# ConectoresEntrada.net
KiCad netlist of a schematic drawn in Altium Designer
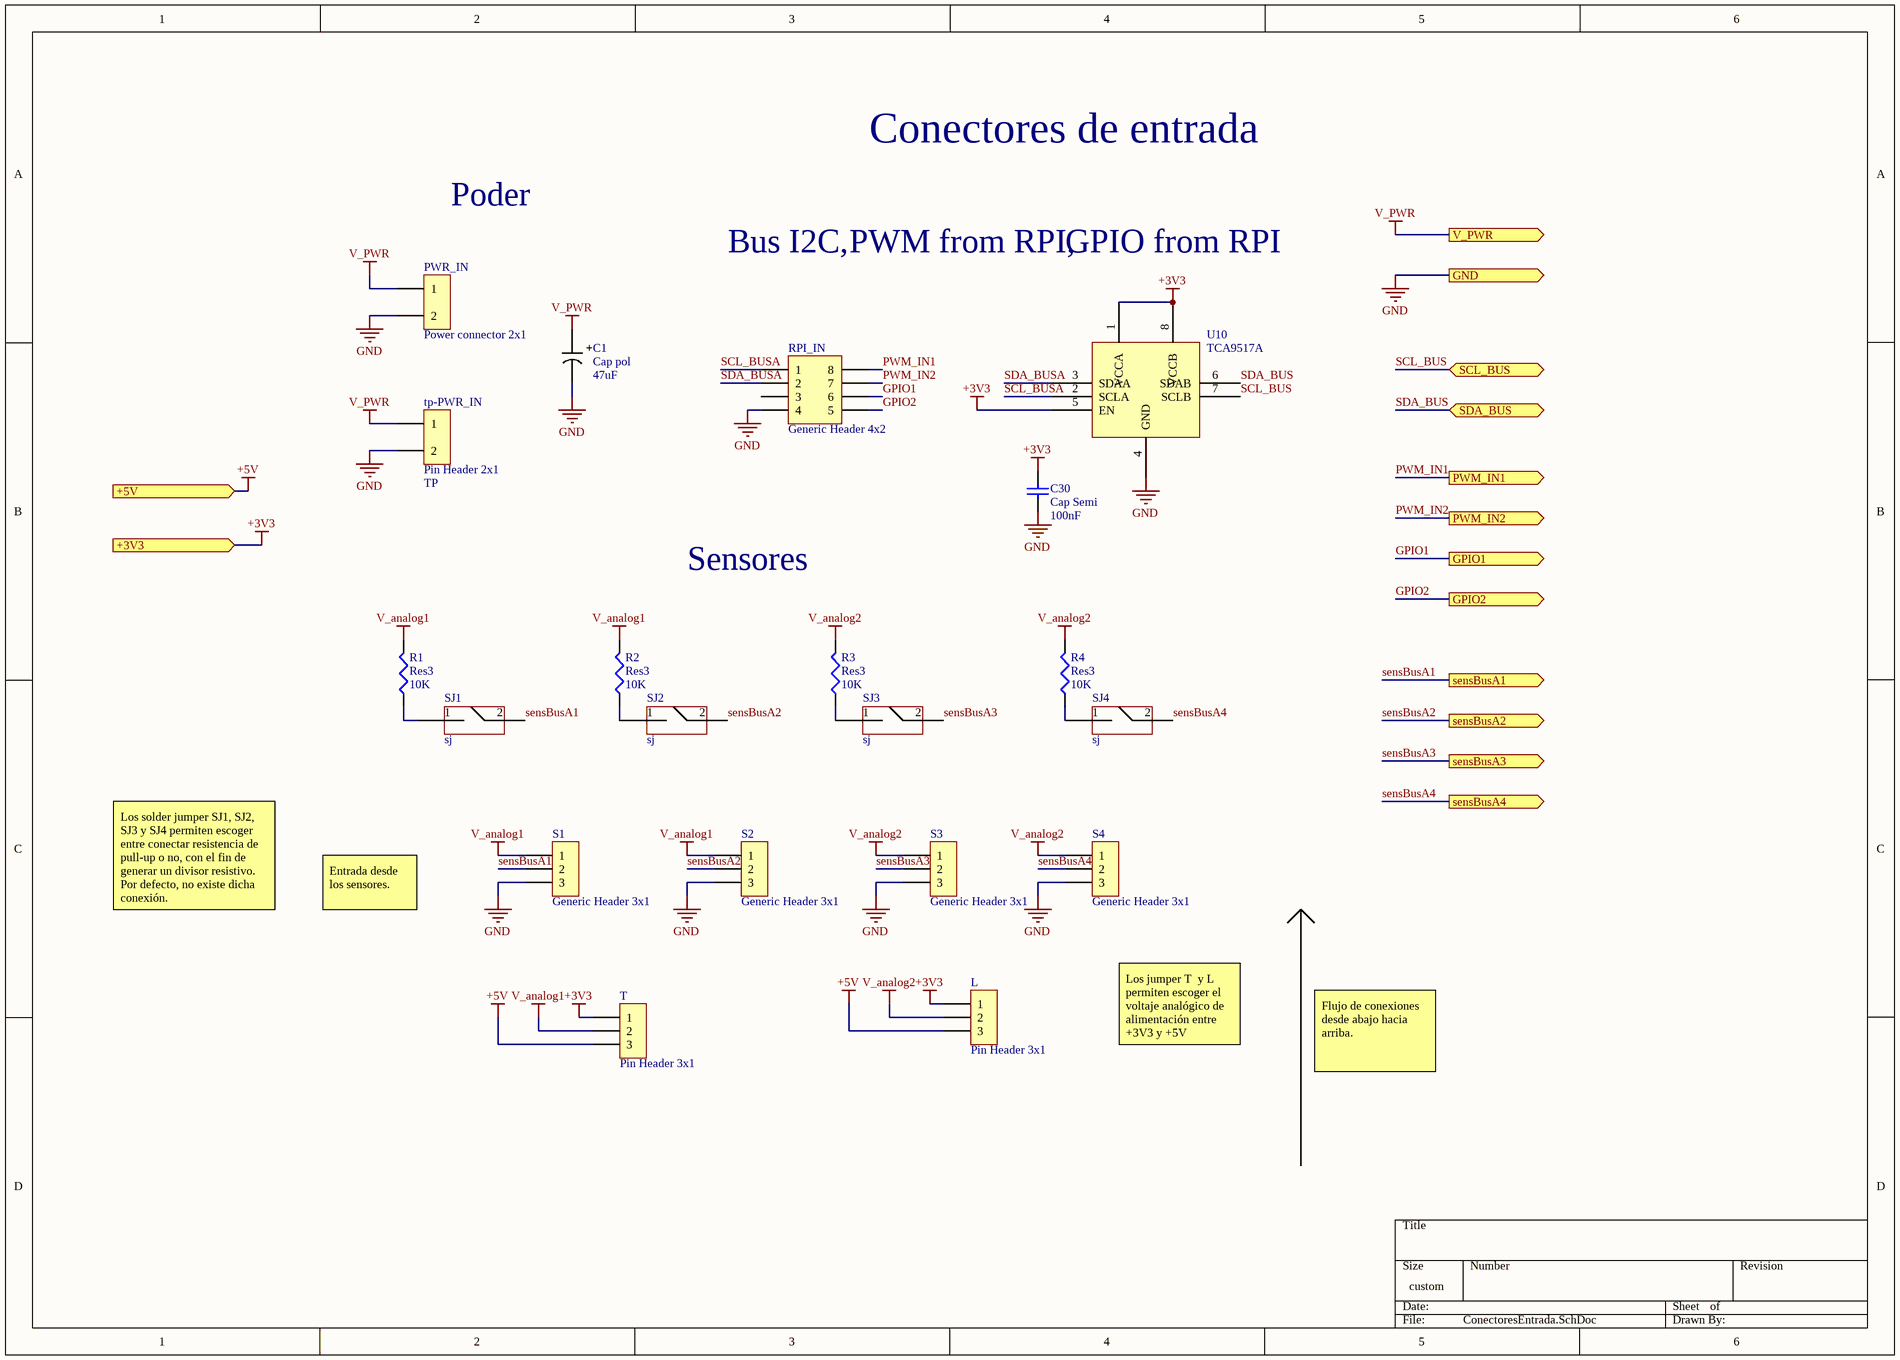
[diagram p0: ConectoresEntrada.SchDoc]

(export (version "E")
  (design (tool "Eeschema 10.0.6"))
  (components
    (comp (ref "C1")
      (value "Cap pol")
      (footprint "CAP_SMD_Electrolytic_10x10")
      (description "Electrolytic Aluminium Capacitor")
      (fields
        (field (name "MANUFACTURER") "Lelon")
        (field (name "MANUFACTURER PART NUMBER") "VEJ470M1HTR-1010")
        (field (name "ALTIUM_VALUE") "47uF")
      )
      (libsource (lib "IoWLabs") (part "Cap pol"))
    )
    (comp (ref "C30")
      (value "Cap Semi")
      (footprint "1608[0603]")
      (description "Capacitor (Semiconductor SIM Model)")
      (fields
        (field (name "ALTIUM_VALUE") "100nF")
        (field (name "MANUFACTURER") "Taiyo Yuden")
        (field (name "MANUFACTURER PART NUMBER") "UMK107B104KAHT")
        (field (name "PUBLISHER") "Altium Limited")
      )
      (libsource (lib "Miscellaneous Devices") (part "Cap Semi"))
    )
    (comp (ref "L")
      (value "Pin Header 3x1")
      (footprint "HDR-TH_3P-P2.54-V")
      (description "Pin Header 3pos, 1 row, 2.54 pitch")
      (fields
        (field (name "MANUFACTURER") "CJT(Changjiang Connectors)")
        (field (name "MANUFACTURER PART NUMBER") "A2541WV-3P")
      )
      (libsource (lib "IoWLabsConnectors") (part "Header - 3x1c"))
    )
    (comp (ref "PWR_IN")
      (value "Power connector 2x1")
      (footprint "CONN-TH_430450212")
      (description "Generic Header Power 2pos")
      (fields (field (name "MANUFACTURER") "MOLEX") (field (name "MANUFACTURER PART NUMBER") "430450212"))
      (libsource (lib "IoWLabsConnectors") (part "PC - 2X1"))
    )
    (comp (ref "R1")
      (value "Res3")
      (footprint "J1-0603")
      (description "Resistor")
      (fields
        (field (name "ALTIUM_VALUE") "10K")
        (field (name "MANUFACTURER") "PANASONIC")
        (field (name "MANUFACTURER PART NUMBER") "ERJPB3B1002V")
        (field (name "PUBLISHER") "Altium Limited")
      )
      (libsource (lib "Miscellaneous Devices") (part "Res3"))
    )
    (comp (ref "R2")
      (value "Res3")
      (footprint "J1-0603")
      (description "Resistor")
      (fields
        (field (name "ALTIUM_VALUE") "10K")
        (field (name "MANUFACTURER") "PANASONIC")
        (field (name "MANUFACTURER PART NUMBER") "ERJPB3B1002V")
        (field (name "PUBLISHER") "Altium Limited")
      )
      (libsource (lib "Miscellaneous Devices") (part "Res3"))
    )
    (comp (ref "R3")
      (value "Res3")
      (footprint "J1-0603")
      (description "Resistor")
      (fields
        (field (name "ALTIUM_VALUE") "10K")
        (field (name "MANUFACTURER") "PANASONIC")
        (field (name "MANUFACTURER PART NUMBER") "ERJPB3B1002V")
        (field (name "PUBLISHER") "Altium Limited")
      )
      (libsource (lib "Miscellaneous Devices") (part "Res3"))
    )
    (comp (ref "R4")
      (value "Res3")
      (footprint "J1-0603")
      (description "Resistor")
      (fields
        (field (name "ALTIUM_VALUE") "10K")
        (field (name "MANUFACTURER PART NUMBER") "ERJPB3B1002V")
        (field (name "MANUFACTURER") "PANASONIC")
        (field (name "PUBLISHER") "Altium Limited")
      )
      (libsource (lib "Miscellaneous Devices") (part "Res3"))
    )
    (comp (ref "RPI_IN")
      (value "Generic Header 4x2")
      (footprint "CONN-TH_8P-P2.54-V-M_15477608")
      (description "Generic Header 8 pos, 2 row, 2.54 pitch")
      (fields (field (name "MANUFACTURER") "MOLEX") (field (name "MANUFACTURER PART NUMBER") "15477608"))
      (libsource (lib "IoWLabsConnectors") (part "Header - 4x2"))
    )
    (comp (ref "S1")
      (value "Generic Header 3x1")
      (footprint "CONN-TH_A2547WV-3P")
      (description "Generic Header 3pos, 1 row, 2.54 pitch")
      (fields
        (field (name "MANUFACTURER") "CJT(Changjiang Connectors)")
        (field (name "MANUFACTURER PART NUMBER") "A2547WV-3P")
      )
      (libsource (lib "IoWLabsConnectors") (part "Header - 3x1"))
    )
    (comp (ref "S2")
      (value "Generic Header 3x1")
      (footprint "CONN-TH_A2547WV-3P")
      (description "Generic Header 3pos, 1 row, 2.54 pitch")
      (fields
        (field (name "MANUFACTURER") "CJT(Changjiang Connectors)")
        (field (name "MANUFACTURER PART NUMBER") "A2547WV-3P")
      )
      (libsource (lib "IoWLabsConnectors") (part "Header - 3x1"))
    )
    (comp (ref "S3")
      (value "Generic Header 3x1")
      (footprint "CONN-TH_A2547WV-3P")
      (description "Generic Header 3pos, 1 row, 2.54 pitch")
      (fields
        (field (name "MANUFACTURER") "CJT(Changjiang Connectors)")
        (field (name "MANUFACTURER PART NUMBER") "A2547WV-3P")
      )
      (libsource (lib "IoWLabsConnectors") (part "Header - 3x1"))
    )
    (comp (ref "S4")
      (value "Generic Header 3x1")
      (footprint "CONN-TH_A2547WV-3P")
      (description "Generic Header 3pos, 1 row, 2.54 pitch")
      (fields
        (field (name "MANUFACTURER") "CJT(Changjiang Connectors)")
        (field (name "MANUFACTURER PART NUMBER") "A2547WV-3P")
      )
      (libsource (lib "IoWLabsConnectors") (part "Header - 3x1"))
    )
    (comp (ref "SJ1")
      (value "sj")
      (footprint "SJ2")
      (description "solder jumper generic")
      (libsource (lib "IoWLabs") (part "Jumper"))
    )
    (comp (ref "SJ2")
      (value "sj")
      (footprint "SJ2")
      (description "solder jumper generic")
      (libsource (lib "IoWLabs") (part "Jumper"))
    )
    (comp (ref "SJ3")
      (value "sj")
      (footprint "SJ2")
      (description "solder jumper generic")
      (libsource (lib "IoWLabs") (part "Jumper"))
    )
    (comp (ref "SJ4")
      (value "sj")
      (footprint "SJ2")
      (description "solder jumper generic")
      (libsource (lib "IoWLabs") (part "Jumper"))
    )
    (comp (ref "T")
      (value "Pin Header 3x1")
      (footprint "HDR-TH_3P-P2.54-V")
      (description "Pin Header 3pos, 1 row, 2.54 pitch")
      (fields
        (field (name "MANUFACTURER") "CJT(Changjiang Connectors)")
        (field (name "MANUFACTURER PART NUMBER") "A2541WV-3P")
      )
      (libsource (lib "IoWLabsConnectors") (part "Header - 3x1c"))
    )
    (comp (ref "tp-PWR_IN")
      (value "Pin Header 2x1")
      (footprint "HDR-TH_P2.54-H-M_A2541WV-2P")
      (description "Pin Header 2pos, 1 row, 2.54 pitch")
      (fields
        (field (name "MANUFACTURER") "CJT(Changjiang Connectors)")
        (field (name "MANUFACTURER PART NUMBER") "A2541WV-2P")
      )
      (libsource (lib "IoWLabsConnectors") (part "Header - 2x1c"))
    )
    (comp (ref "U10")
      (value "TCA9517A")
      (footprint "VSSOP - 8")
      (description "VSSOP-8_3x3x065P Level Translators, Shifters RoHS")
      (fields
        (field (name "MANUFACTURER") "Texas Instruments")
        (field (name "MANUFACTURER PART NUMBER") "TCA9517ADGKR")
      )
      (libsource (lib "IoWLabs") (part "TCA9517A"))
    )
  )
  (nets
    (net (code "1") (name "+3V3") (class "Default")
      (node (ref "C30") (pin "2") (pinfunction "2_2") (pintype "passive"))
      (node (ref "L") (pin "1") (pinfunction "1_1") (pintype "passive"))
      (node (ref "T") (pin "1") (pinfunction "1_1") (pintype "passive"))
      (node (ref "U10") (pin "1") (pinfunction "VCCA_1") (pintype "passive"))
      (node (ref "U10") (pin "5") (pinfunction "EN_5") (pintype "passive"))
      (node (ref "U10") (pin "8") (pinfunction "VCCB_8") (pintype "passive"))
    )
    (net (code "2") (name "+5V") (class "Default")
      (node (ref "L") (pin "3") (pinfunction "3_3") (pintype "passive"))
      (node (ref "T") (pin "3") (pinfunction "3_3") (pintype "passive"))
    )
    (net (code "3") (name "/GPIO1") (class "Default")
      (node (ref "RPI_IN") (pin "6") (pinfunction "6_6") (pintype "passive"))
    )
    (net (code "4") (name "/GPIO2") (class "Default")
      (node (ref "RPI_IN") (pin "5") (pinfunction "5_5") (pintype "passive"))
    )
    (net (code "5") (name "/PWM_IN1") (class "Default")
      (node (ref "RPI_IN") (pin "8") (pinfunction "8_8") (pintype "passive"))
    )
    (net (code "6") (name "/PWM_IN2") (class "Default")
      (node (ref "RPI_IN") (pin "7") (pinfunction "7_7") (pintype "passive"))
    )
    (net (code "7") (name "/SCL_BUS") (class "Default")
      (node (ref "U10") (pin "7") (pinfunction "SCLB_7") (pintype "passive"))
    )
    (net (code "8") (name "/SCL_BUSA") (class "Default")
      (node (ref "RPI_IN") (pin "1") (pinfunction "1_1") (pintype "passive"))
      (node (ref "U10") (pin "2") (pinfunction "SCLA_2") (pintype "passive"))
    )
    (net (code "9") (name "/SDA_BUS") (class "Default")
      (node (ref "U10") (pin "6") (pinfunction "SDAB_6") (pintype "passive"))
    )
    (net (code "10") (name "/SDA_BUSA") (class "Default")
      (node (ref "RPI_IN") (pin "2") (pinfunction "2_2") (pintype "passive"))
      (node (ref "U10") (pin "3") (pinfunction "SDAA_3") (pintype "passive"))
    )
    (net (code "11") (name "/sensBusA1") (class "Default")
      (node (ref "S1") (pin "2") (pinfunction "2_2") (pintype "passive"))
      (node (ref "SJ1") (pin "2") (pinfunction "2_2") (pintype "passive"))
    )
    (net (code "12") (name "/sensBusA2") (class "Default")
      (node (ref "S2") (pin "2") (pinfunction "2_2") (pintype "passive"))
      (node (ref "SJ2") (pin "2") (pinfunction "2_2") (pintype "passive"))
    )
    (net (code "13") (name "/sensBusA3") (class "Default")
      (node (ref "S3") (pin "2") (pinfunction "2_2") (pintype "passive"))
      (node (ref "SJ3") (pin "2") (pinfunction "2_2") (pintype "passive"))
    )
    (net (code "14") (name "/sensBusA4") (class "Default")
      (node (ref "S4") (pin "2") (pinfunction "2_2") (pintype "passive"))
      (node (ref "SJ4") (pin "2") (pinfunction "2_2") (pintype "passive"))
    )
    (net (code "15") (name "GND") (class "Default")
      (node (ref "C1") (pin "1") (pinfunction "1_1") (pintype "passive"))
      (node (ref "C30") (pin "1") (pinfunction "1_1") (pintype "passive"))
      (node (ref "PWR_IN") (pin "2") (pinfunction "2_2") (pintype "passive"))
      (node (ref "RPI_IN") (pin "4") (pinfunction "4_4") (pintype "passive"))
      (node (ref "S1") (pin "3") (pinfunction "3_3") (pintype "passive"))
      (node (ref "S2") (pin "3") (pinfunction "3_3") (pintype "passive"))
      (node (ref "S3") (pin "3") (pinfunction "3_3") (pintype "passive"))
      (node (ref "S4") (pin "3") (pinfunction "3_3") (pintype "passive"))
      (node (ref "U10") (pin "4") (pinfunction "GND_4") (pintype "passive"))
      (node (ref "tp-PWR_IN") (pin "2") (pinfunction "2_2") (pintype "passive"))
    )
    (net (code "16") (name "Net-(R1-Pad1)") (class "Default")
      (node (ref "R1") (pin "1") (pinfunction "1_1") (pintype "passive"))
      (node (ref "SJ1") (pin "1") (pinfunction "1_1") (pintype "passive"))
    )
    (net (code "17") (name "Net-(R2-Pad1)") (class "Default")
      (node (ref "R2") (pin "1") (pinfunction "1_1") (pintype "passive"))
      (node (ref "SJ2") (pin "1") (pinfunction "1_1") (pintype "passive"))
    )
    (net (code "18") (name "Net-(R3-Pad1)") (class "Default")
      (node (ref "R3") (pin "1") (pinfunction "1_1") (pintype "passive"))
      (node (ref "SJ3") (pin "1") (pinfunction "1_1") (pintype "passive"))
    )
    (net (code "19") (name "Net-(R4-Pad1)") (class "Default")
      (node (ref "R4") (pin "1") (pinfunction "1_1") (pintype "passive"))
      (node (ref "SJ4") (pin "1") (pinfunction "1_1") (pintype "passive"))
    )
    (net (code "20") (name "V_PWR") (class "Default")
      (node (ref "C1") (pin "2") (pinfunction "2_2") (pintype "passive"))
      (node (ref "PWR_IN") (pin "1") (pinfunction "1_1") (pintype "passive"))
      (node (ref "tp-PWR_IN") (pin "1") (pinfunction "1_1") (pintype "passive"))
    )
    (net (code "21") (name "V_analog1") (class "Default")
      (node (ref "R1") (pin "2") (pinfunction "2_2") (pintype "passive"))
      (node (ref "R2") (pin "2") (pinfunction "2_2") (pintype "passive"))
      (node (ref "S1") (pin "1") (pinfunction "1_1") (pintype "passive"))
      (node (ref "S2") (pin "1") (pinfunction "1_1") (pintype "passive"))
      (node (ref "T") (pin "2") (pinfunction "2_2") (pintype "passive"))
    )
    (net (code "22") (name "V_analog2") (class "Default")
      (node (ref "L") (pin "2") (pinfunction "2_2") (pintype "passive"))
      (node (ref "R3") (pin "2") (pinfunction "2_2") (pintype "passive"))
      (node (ref "R4") (pin "2") (pinfunction "2_2") (pintype "passive"))
      (node (ref "S3") (pin "1") (pinfunction "1_1") (pintype "passive"))
      (node (ref "S4") (pin "1") (pinfunction "1_1") (pintype "passive"))
    )
    (net (code "23") (name "unconnected-(RPI_IN-Pad3)") (class "Default")
      (node (ref "RPI_IN") (pin "3") (pinfunction "3_3") (pintype "passive"))
    )
  )
)
